# Power_Resistor.net
KiCad netlist of a schematic drawn in Altium Designer
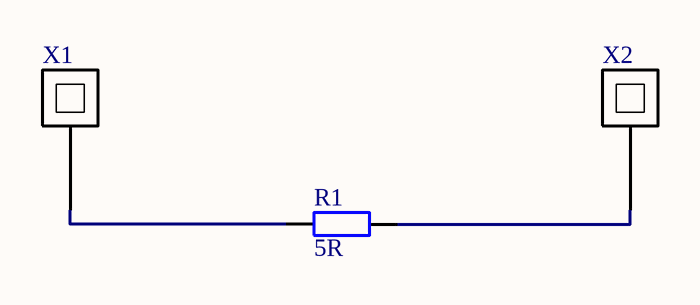
[diagram p0: Power_Resistor.SchDoc]

(export (version "E")
  (design (tool "Eeschema 10.0.6"))
  (components
    (comp (ref "R1")
      (value "5R")
      (footprint "AXIAL-0.9")
      (description "Res 270R")
      (fields (field (name "PART NUMBER") "ERJ6ENF2703V") (field (name "MANUFACTURER") "Panasonic"))
      (libsource (lib "2121_Robot3roues_V2.0") (part "RES"))
    )
    (comp (ref "X1")
      (value "3V3")
      (footprint "PIN1")
      (description "CONN HEADER VERT 1POS")
      (libsource (lib "2019_RegThermiqueMyRio") (part "Berg"))
    )
    (comp (ref "X2")
      (value "3V3")
      (footprint "PIN1")
      (description "CONN HEADER VERT 1POS")
      (libsource (lib "2019_RegThermiqueMyRio") (part "Berg"))
    )
  )
  (nets
    (net (code "1") (name "Net-(R1-Pad1)") (class "Default")
      (node (ref "R1") (pin "1") (pinfunction "1_1") (pintype "passive"))
      (node (ref "X2") (pin "1") (pinfunction "1_1") (pintype "passive"))
    )
    (net (code "2") (name "Net-(R1-Pad2)") (class "Default")
      (node (ref "R1") (pin "2") (pinfunction "2_2") (pintype "passive"))
      (node (ref "X1") (pin "1") (pinfunction "1_1") (pintype "passive"))
    )
  )
)
